# Power_5V-8A.net
KiCad netlist of a schematic drawn in EAGLE
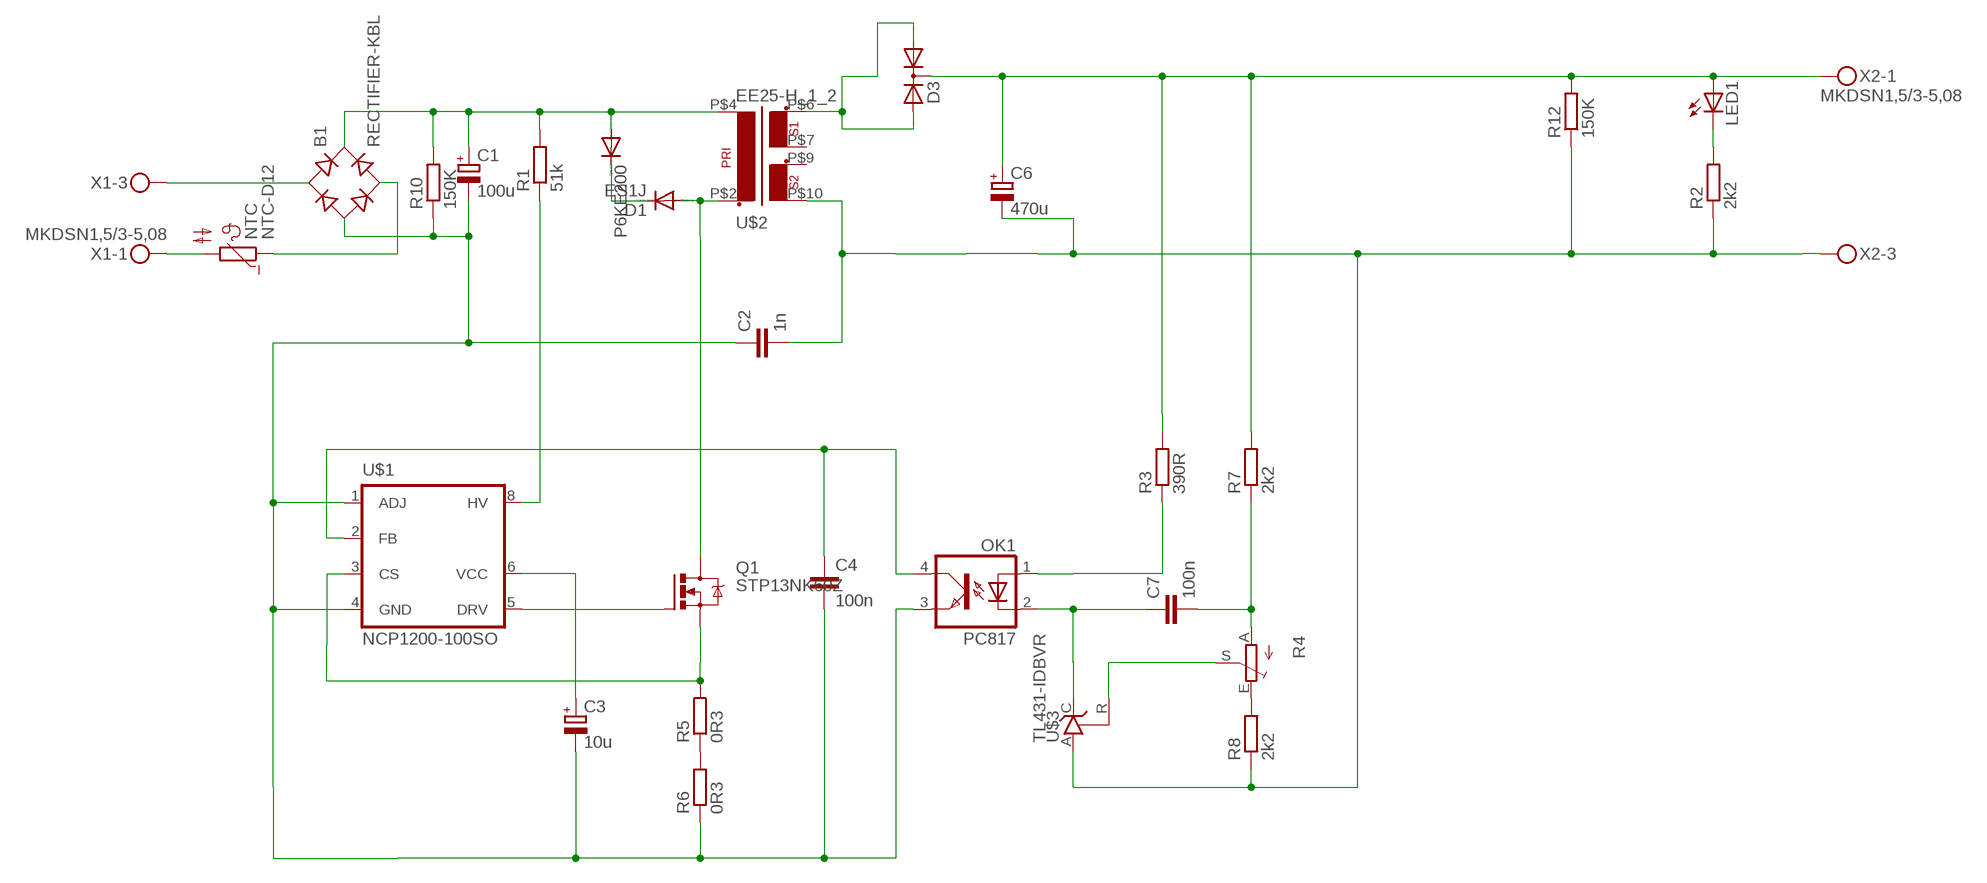
[diagram p0: schematic, sheet 1]

(export (version "E")
  (design (tool "Eeschema 10.0.6"))
  (components
    (comp (ref "B1")
      (value "RECTIFIER-KBL")
      (footprint "eagle-import:KBL")
      (libsource (lib "eagle-import") (part "RECTIFIER-KBL"))
    )
    (comp (ref "C1")
      (value "100u")
      (footprint "eagle-import:EB22,5D")
      (libsource (lib "eagle-import") (part "CPOL-EUE10-22.5"))
    )
    (comp (ref "C2")
      (value "1n")
      (footprint "eagle-import:C050-024X044")
      (libsource (lib "eagle-import") (part "C-EU050-024X044"))
    )
    (comp (ref "C3")
      (value "10u")
      (footprint "eagle-import:E5-5")
      (libsource (lib "eagle-import") (part "CPOL-EUE5-5"))
    )
    (comp (ref "C4")
      (value "100n")
      (footprint "eagle-import:C0805")
      (libsource (lib "eagle-import") (part "C-EUC0805"))
    )
    (comp (ref "C6")
      (value "470u")
      (footprint "eagle-import:E5-10,5")
      (libsource (lib "eagle-import") (part "CPOL-EUE5-10.5"))
    )
    (comp (ref "C7")
      (value "100n")
      (footprint "eagle-import:C0805")
      (libsource (lib "eagle-import") (part "C-EUC0805"))
    )
    (comp (ref "D1")
      (value "ES1J")
      (footprint "eagle-import:DO41-7.6")
      (libsource (lib "eagle-import") (part "DIODE-DO41-7.6"))
    )
    (comp (ref "D3")
      (value "DIODE-2AC|CATO220V")
      (footprint "eagle-import:TO220ABS")
      (libsource (lib "eagle-import") (part "DIODE-2AC|CATO220V"))
    )
    (comp (ref "LED1")
      (value "LED5MM")
      (footprint "eagle-import:LED5MM")
      (libsource (lib "eagle-import") (part "LED5MM"))
    )
    (comp (ref "NTC")
      (value "NTC-D12")
      (footprint "eagle-import:NTC-D12")
      (libsource (lib "eagle-import") (part "NTC-D12"))
    )
    (comp (ref "OK1")
      (value "PC817")
      (footprint "eagle-import:DIL04")
      (fields (field (name "MPN") "PC817X4J000F"))
      (libsource (lib "eagle-import") (part "PC817"))
    )
    (comp (ref "P6KE200")
      (value "DIODE-DO15-12")
      (footprint "eagle-import:DO15-12")
      (libsource (lib "eagle-import") (part "DIODE-DO15-12"))
    )
    (comp (ref "Q1")
      (value "STP13NK60Z")
      (footprint "eagle-import:TO220BV")
      (libsource (lib "eagle-import") (part "IRF740"))
    )
    (comp (ref "R1")
      (value "51k")
      (footprint "eagle-import:SQP-5")
      (libsource (lib "eagle-import") (part "R_SQP-5"))
    )
    (comp (ref "R2")
      (value "2k2")
      (footprint "eagle-import:R1206")
      (libsource (lib "eagle-import") (part "R-EU_R1206"))
    )
    (comp (ref "R3")
      (value "390R")
      (footprint "eagle-import:R1206")
      (libsource (lib "eagle-import") (part "R-EU_R1206"))
    )
    (comp (ref "R4")
      (value "TRIM_EU-S75H")
      (footprint "eagle-import:S75H")
      (libsource (lib "eagle-import") (part "TRIM_EU-S75H"))
    )
    (comp (ref "R5")
      (value "0R3")
      (footprint "eagle-import:0411_12")
      (libsource (lib "eagle-import") (part "R-EU_0411/12"))
    )
    (comp (ref "R6")
      (value "0R3")
      (footprint "eagle-import:0411_12")
      (libsource (lib "eagle-import") (part "R-EU_0411/12"))
    )
    (comp (ref "R7")
      (value "2k2")
      (footprint "eagle-import:R1206")
      (libsource (lib "eagle-import") (part "R-EU_R1206"))
    )
    (comp (ref "R8")
      (value "2k2")
      (footprint "eagle-import:R1206")
      (libsource (lib "eagle-import") (part "R-EU_R1206"))
    )
    (comp (ref "R10")
      (value "150K")
      (footprint "eagle-import:0207_10")
      (libsource (lib "eagle-import") (part "R-EU_0207/10"))
    )
    (comp (ref "R12")
      (value "150K")
      (footprint "eagle-import:R1206")
      (libsource (lib "eagle-import") (part "R-EU_R1206"))
    )
    (comp (ref "U$1")
      (value "NCP1200-100SO")
      (footprint "eagle-import:SOP8")
      (libsource (lib "eagle-import") (part "NCP1200-100SO"))
    )
    (comp (ref "U$2")
      (value "EE25-H_1_2")
      (footprint "eagle-import:EE25")
      (libsource (lib "eagle-import") (part "EE25-H_1_2"))
    )
    (comp (ref "U$3")
      (value "TL431-IDBVR")
      (footprint "eagle-import:SOT23-5")
      (libsource (lib "eagle-import") (part "TL431-IDBVR"))
    )
    (comp (ref "X1")
      (value "MKDSN1,5/3-5,08")
      (footprint "eagle-import:MKDSN1,5_3-5,08")
      (libsource (lib "eagle-import") (part "MKDSN1,5/3-5,08"))
    )
    (comp (ref "X2")
      (value "MKDSN1,5/3-5,08")
      (footprint "eagle-import:MKDSN1,5_3-5,08")
      (libsource (lib "eagle-import") (part "MKDSN1,5/3-5,08"))
    )
  )
  (nets
    (net (code "1") (name "Net-(B1-PadAC2)") (class "Default")
      (node (ref "B1") (pin "AC2") (pinfunction "AC2_AC2") (pintype "passive"))
      (node (ref "NTC") (pin "1") (pinfunction "1_1") (pintype "passive"))
    )
    (net (code "2") (name "Net-(C7-Pad2)") (class "Default")
      (node (ref "C7") (pin "2") (pinfunction "2_2") (pintype "passive"))
      (node (ref "R4") (pin "A") (pinfunction "A_A") (pintype "passive"))
      (node (ref "R7") (pin "1") (pinfunction "1_1") (pintype "passive"))
    )
    (net (code "3") (name "Net-(D1-PadC)") (class "Default")
      (node (ref "D1") (pin "C") (pinfunction "C_C") (pintype "passive"))
      (node (ref "P6KE200") (pin "C") (pinfunction "C_C") (pintype "passive"))
    )
    (net (code "4") (name "Net-(LED1-C)") (class "Default")
      (node (ref "LED1") (pin "K") (pinfunction "C_K") (pintype "passive"))
      (node (ref "R2") (pin "2") (pinfunction "2_2") (pintype "passive"))
    )
    (net (code "5") (name "Net-(OK1-A)") (class "Default")
      (node (ref "OK1") (pin "1") (pinfunction "A_1") (pintype "passive"))
      (node (ref "R3") (pin "1") (pinfunction "1_1") (pintype "passive"))
    )
    (net (code "6") (name "Net-(OK1-C)") (class "Default")
      (node (ref "C7") (pin "1") (pinfunction "1_1") (pintype "passive"))
      (node (ref "OK1") (pin "2") (pinfunction "C_2") (pintype "passive"))
      (node (ref "U$3") (pin "C") (pinfunction "C_C") (pintype "passive"))
    )
    (net (code "7") (name "Net-(OK1-COL)") (class "Default")
      (node (ref "C4") (pin "1") (pinfunction "1_1") (pintype "passive"))
      (node (ref "OK1") (pin "4") (pinfunction "COL_4") (pintype "passive"))
      (node (ref "U$1") (pin "2") (pinfunction "FB_2") (pintype "input"))
    )
    (net (code "8") (name "Net-(OK1-EMIT)") (class "Default")
      (node (ref "B1") (pin "-") (pinfunction "-_-") (pintype "passive"))
      (node (ref "C1") (pin "-") (pinfunction "-_-") (pintype "passive"))
      (node (ref "C2") (pin "1") (pinfunction "1_1") (pintype "passive"))
      (node (ref "C3") (pin "-") (pinfunction "-_-") (pintype "passive"))
      (node (ref "C4") (pin "2") (pinfunction "2_2") (pintype "passive"))
      (node (ref "OK1") (pin "3") (pinfunction "EMIT_3") (pintype "passive"))
      (node (ref "R10") (pin "1") (pinfunction "1_1") (pintype "passive"))
      (node (ref "R6") (pin "1") (pinfunction "1_1") (pintype "passive"))
      (node (ref "U$1") (pin "1") (pinfunction "ADJ_1") (pintype "passive"))
      (node (ref "U$1") (pin "4") (pinfunction "GND_4") (pintype "passive"))
    )
    (net (code "9") (name "Net-(R4-PadE)") (class "Default")
      (node (ref "R4") (pin "E") (pinfunction "E_E") (pintype "passive"))
      (node (ref "R8") (pin "2") (pinfunction "2_2") (pintype "passive"))
    )
    (net (code "10") (name "Net-(R4-PadS)") (class "Default")
      (node (ref "R4") (pin "S") (pinfunction "S_S") (pintype "passive"))
      (node (ref "U$3") (pin "R") (pinfunction "R_R") (pintype "passive"))
    )
    (net (code "11") (name "Net-(R5-Pad1)") (class "Default")
      (node (ref "R5") (pin "1") (pinfunction "1_1") (pintype "passive"))
      (node (ref "R6") (pin "2") (pinfunction "2_2") (pintype "passive"))
    )
    (net (code "12") (name "Net-(U$1-CS)") (class "Default")
      (node (ref "Q1") (pin "S") (pinfunction "S_S") (pintype "passive"))
      (node (ref "R5") (pin "2") (pinfunction "2_2") (pintype "passive"))
      (node (ref "U$1") (pin "3") (pinfunction "CS_3") (pintype "input"))
    )
    (net (code "13") (name "Net-(U$1-DRV)") (class "Default")
      (node (ref "Q1") (pin "G") (pinfunction "G_G") (pintype "passive"))
      (node (ref "U$1") (pin "5") (pinfunction "DRV_5") (pintype "power_in"))
    )
    (net (code "14") (name "Net-(U$1-HV)") (class "Default")
      (node (ref "R1") (pin "1") (pinfunction "1_1") (pintype "passive"))
      (node (ref "U$1") (pin "8") (pinfunction "HV_8") (pintype "passive"))
    )
    (net (code "15") (name "Net-(U$1-VCC)") (class "Default")
      (node (ref "C3") (pin "+") (pinfunction "+_+") (pintype "passive"))
      (node (ref "U$1") (pin "6") (pinfunction "VCC_6") (pintype "output"))
    )
    (net (code "16") (name "Net-(U$2-1)") (class "Default")
      (node (ref "D1") (pin "A") (pinfunction "A_A") (pintype "passive"))
      (node (ref "Q1") (pin "D") (pinfunction "D_D") (pintype "passive"))
      (node (ref "U$2") (pin "P$2") (pinfunction "1_P$2") (pintype "passive"))
    )
    (net (code "17") (name "Net-(U$2-2)") (class "Default")
      (node (ref "B1") (pin "+") (pinfunction "+_+") (pintype "passive"))
      (node (ref "C1") (pin "+") (pinfunction "+_+") (pintype "passive"))
      (node (ref "P6KE200") (pin "A") (pinfunction "A_A") (pintype "passive"))
      (node (ref "R1") (pin "2") (pinfunction "2_2") (pintype "passive"))
      (node (ref "R10") (pin "2") (pinfunction "2_2") (pintype "passive"))
      (node (ref "U$2") (pin "P$4") (pinfunction "2_P$4") (pintype "passive"))
    )
    (net (code "18") (name "Net-(U$2-3)") (class "Default")
      (node (ref "D3") (pin "A1") (pinfunction "A1_A1") (pintype "passive"))
      (node (ref "D3") (pin "A2") (pinfunction "A2_A2") (pintype "passive"))
      (node (ref "U$2") (pin "P$6") (pinfunction "3_P$6") (pintype "passive"))
    )
    (net (code "19") (name "Net-(U$2-6)") (class "Default")
      (node (ref "C2") (pin "2") (pinfunction "2_2") (pintype "passive"))
      (node (ref "C6") (pin "-") (pinfunction "-_-") (pintype "passive"))
      (node (ref "R12") (pin "1") (pinfunction "1_1") (pintype "passive"))
      (node (ref "R2") (pin "1") (pinfunction "1_1") (pintype "passive"))
      (node (ref "R8") (pin "1") (pinfunction "1_1") (pintype "passive"))
      (node (ref "U$2") (pin "P$10") (pinfunction "6_P$10") (pintype "passive"))
      (node (ref "U$3") (pin "A") (pinfunction "A_A") (pintype "passive"))
      (node (ref "X2") (pin "3") (pinfunction "KL_3") (pintype "passive"))
    )
    (net (code "20") (name "Net-(X1A-KL)") (class "Default")
      (node (ref "NTC") (pin "2") (pinfunction "2_2") (pintype "passive"))
      (node (ref "X1") (pin "1") (pinfunction "KL_1") (pintype "passive"))
    )
    (net (code "21") (name "Net-(X1C-KL)") (class "Default")
      (node (ref "B1") (pin "AC1") (pinfunction "AC1_AC1") (pintype "passive"))
      (node (ref "X1") (pin "3") (pinfunction "KL_3") (pintype "passive"))
    )
    (net (code "22") (name "Net-(X2A-KL)") (class "Default")
      (node (ref "C6") (pin "+") (pinfunction "+_+") (pintype "passive"))
      (node (ref "D3") (pin "C") (pinfunction "C_C") (pintype "passive"))
      (node (ref "LED1") (pin "A") (pinfunction "A_A") (pintype "passive"))
      (node (ref "R12") (pin "2") (pinfunction "2_2") (pintype "passive"))
      (node (ref "R3") (pin "2") (pinfunction "2_2") (pintype "passive"))
      (node (ref "R7") (pin "2") (pinfunction "2_2") (pintype "passive"))
      (node (ref "X2") (pin "1") (pinfunction "KL_1") (pintype "passive"))
    )
    (net (code "23") (name "unconnected-(U$2-4-PadP$7)") (class "Default")
      (node (ref "U$2") (pin "P$7") (pinfunction "4_P$7") (pintype "passive"))
    )
    (net (code "24") (name "unconnected-(U$2-5-PadP$9)") (class "Default")
      (node (ref "U$2") (pin "P$9") (pinfunction "5_P$9") (pintype "passive"))
    )
  )
)
